# FP_connectors.net
KiCad netlist of a schematic drawn in Altium Designer
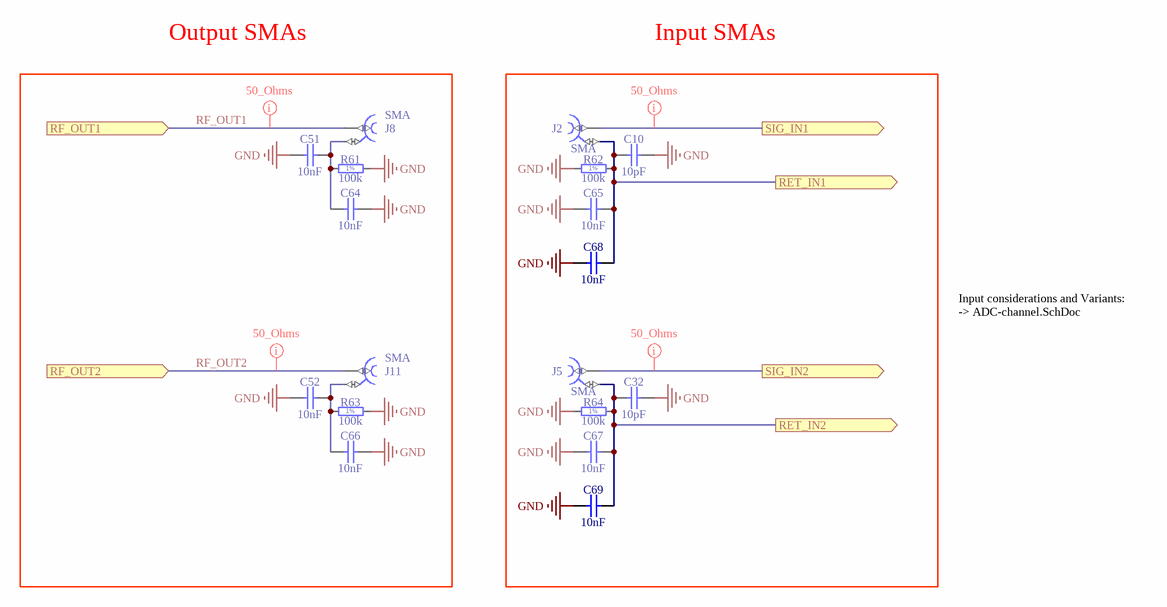
[diagram p0: FP_connectors.SchDoc]

(export (version "E")
  (design (tool "Eeschema 10.0.6"))
  (components
    (comp (ref "C10")
      (value "10pF")
      (footprint "CAPC1005X55N")
      (description "Non-polarised capacitor")
      (fields
        (field (name "PART NUMBER") "CC0402_10PF_50V_5%_C0G")
        (field (name "VOLTAGE") "50V")
        (field (name "AUTHOR") "CERN DEM JLC")
      )
      (libsource (lib "Capacitors") (part "Capacitor - non polarized"))
    )
    (comp (ref "C32")
      (value "10pF")
      (footprint "CAPC1005X55N")
      (description "Non-polarised capacitor")
      (fields
        (field (name "PART NUMBER") "CC0402_10PF_50V_5%_C0G")
        (field (name "VOLTAGE") "50V")
        (field (name "AUTHOR") "CERN DEM JLC")
      )
      (libsource (lib "Capacitors") (part "Capacitor - non polarized"))
    )
    (comp (ref "C51")
      (value "10nF")
      (footprint "CAPC1005X55N")
      (description "Non-polarised capacitor")
      (fields
        (field (name "PART NUMBER") "CC0402_10NF_16V_10%_X7R")
        (field (name "VOLTAGE") "16V")
        (field (name "AUTHOR") "CERN DEM JLC")
      )
      (libsource (lib "Capacitors") (part "Capacitor - non polarized"))
    )
    (comp (ref "C52")
      (value "10nF")
      (footprint "CAPC1005X55N")
      (description "Non-polarised capacitor")
      (fields
        (field (name "PART NUMBER") "CC0402_10NF_16V_10%_X7R")
        (field (name "VOLTAGE") "16V")
        (field (name "AUTHOR") "CERN DEM JLC")
      )
      (libsource (lib "Capacitors") (part "Capacitor - non polarized"))
    )
    (comp (ref "C64")
      (value "10nF")
      (footprint "CAPC1005X55N")
      (description "Non-polarised capacitor")
      (fields
        (field (name "PART NUMBER") "CC0402_10NF_16V_10%_X7R")
        (field (name "VOLTAGE") "16V")
        (field (name "AUTHOR") "CERN DEM JLC")
      )
      (libsource (lib "Capacitors") (part "Capacitor - non polarized"))
    )
    (comp (ref "C65")
      (value "10nF")
      (footprint "CAPC1005X55N")
      (description "Non-polarised capacitor")
      (fields
        (field (name "PART NUMBER") "CC0402_10NF_16V_10%_X7R")
        (field (name "VOLTAGE") "16V")
        (field (name "AUTHOR") "CERN DEM JLC")
      )
      (libsource (lib "Capacitors") (part "Capacitor - non polarized"))
    )
    (comp (ref "C66")
      (value "10nF")
      (footprint "CAPC1005X55N")
      (description "Non-polarised capacitor")
      (fields
        (field (name "PART NUMBER") "CC0402_10NF_16V_10%_X7R")
        (field (name "VOLTAGE") "16V")
        (field (name "AUTHOR") "CERN DEM JLC")
      )
      (libsource (lib "Capacitors") (part "Capacitor - non polarized"))
    )
    (comp (ref "C67")
      (value "10nF")
      (footprint "CAPC1005X55N")
      (description "Non-polarised capacitor")
      (fields
        (field (name "PART NUMBER") "CC0402_10NF_16V_10%_X7R")
        (field (name "VOLTAGE") "16V")
        (field (name "AUTHOR") "CERN DEM JLC")
      )
      (libsource (lib "Capacitors") (part "Capacitor - non polarized"))
    )
    (comp (ref "C68")
      (value "10nF")
      (footprint "CAPC1005X55N")
      (description "Non-polarised capacitor")
      (fields
        (field (name "PART NUMBER") "CC0402_10NF_16V_10%_X7R")
        (field (name "VOLTAGE") "16V")
        (field (name "AUTHOR") "CERN DEM JLC")
      )
      (libsource (lib "Capacitors") (part "Capacitor - non polarized"))
    )
    (comp (ref "C69")
      (value "10nF")
      (footprint "CAPC1005X55N")
      (description "Non-polarised capacitor")
      (fields
        (field (name "PART NUMBER") "CC0402_10NF_16V_10%_X7R")
        (field (name "VOLTAGE") "16V")
        (field (name "AUTHOR") "CERN DEM JLC")
      )
      (libsource (lib "Capacitors") (part "Capacitor - non polarized"))
    )
    (comp (ref "J2")
      (value "SMA")
      (footprint "Telegartner_J01151A0921")
      (description "RiSMA 50 Ohms Right Angle PCB Jack")
      (fields
        (field (name "PART NUMBER") "Telegartner_J01151A0921")
        (field (name "MANUFACTURER") "Telegartner")
        (field (name "AUTHOR") "GK")
      )
      (libsource (lib "LIBRARY_SCH") (part "SMA_RA_J01151A0921"))
    )
    (comp (ref "J5")
      (value "SMA")
      (footprint "Telegartner_J01151A0921")
      (description "RiSMA 50 Ohms Right Angle PCB Jack")
      (fields
        (field (name "PART NUMBER") "Telegartner_J01151A0921")
        (field (name "MANUFACTURER") "Telegartner")
        (field (name "AUTHOR") "GK")
      )
      (libsource (lib "LIBRARY_SCH") (part "SMA_RA_J01151A0921"))
    )
    (comp (ref "J8")
      (value "SMA")
      (footprint "TELEGARTNER_J01151A0451")
      (fields
        (field (name "PART NUMBER") "TELEGARTNER_J01151A0451")
        (field (name "MANUFACTURER") "TELEGARTNER")
        (field (name "MANUFACTURER PART NUMBER") "J01151A0451")
        (field (name "AUTHOR") "CERN DEM JLC")
      )
      (libsource (lib "Connectors") (part "Coax_1Female_1Shield"))
    )
    (comp (ref "J11")
      (value "SMA")
      (footprint "TELEGARTNER_J01151A0451")
      (fields
        (field (name "PART NUMBER") "TELEGARTNER_J01151A0451")
        (field (name "MANUFACTURER") "TELEGARTNER")
        (field (name "MANUFACTURER PART NUMBER") "J01151A0451")
        (field (name "AUTHOR") "CERN DEM JLC")
      )
      (libsource (lib "Connectors") (part "Coax_1Female_1Shield"))
    )
    (comp (ref "R61")
      (value "100k")
      (footprint "RESC1005X40N")
      (description "Resistor - 1%")
      (fields
        (field (name "PART NUMBER") "R0402_100K_1%_0.0625W_100PPM")
        (field (name "POWER") "0.0625W")
        (field (name "AUTHOR") "CERN DEM JLC")
      )
      (libsource (lib "Resistors") (part "Resistor - 1%"))
    )
    (comp (ref "R62")
      (value "100k")
      (footprint "RESC1005X40N")
      (description "Resistor - 1%")
      (fields
        (field (name "PART NUMBER") "R0402_100K_1%_0.0625W_100PPM")
        (field (name "POWER") "0.0625W")
        (field (name "AUTHOR") "CERN DEM JLC")
      )
      (libsource (lib "Resistors") (part "Resistor - 1%"))
    )
    (comp (ref "R63")
      (value "100k")
      (footprint "RESC1005X40N")
      (description "Resistor - 1%")
      (fields
        (field (name "PART NUMBER") "R0402_100K_1%_0.0625W_100PPM")
        (field (name "POWER") "0.0625W")
        (field (name "AUTHOR") "CERN DEM JLC")
      )
      (libsource (lib "Resistors") (part "Resistor - 1%"))
    )
    (comp (ref "R64")
      (value "100k")
      (footprint "RESC1005X40N")
      (description "Resistor - 1%")
      (fields
        (field (name "PART NUMBER") "R0402_100K_1%_0.0625W_100PPM")
        (field (name "POWER") "0.0625W")
        (field (name "AUTHOR") "CERN DEM JLC")
      )
      (libsource (lib "Resistors") (part "Resistor - 1%"))
    )
  )
  (nets
    (net (code "1") (name "/RET_IN1") (class "Default")
      (node (ref "C10") (pin "1") (pinfunction "1_1") (pintype "passive"))
      (node (ref "C65") (pin "2") (pinfunction "2_2") (pintype "passive"))
      (node (ref "C68") (pin "2") (pinfunction "2_2") (pintype "passive"))
      (node (ref "J2") (pin "2") (pinfunction "2_2") (pintype "bidirectional"))
      (node (ref "R62") (pin "2") (pinfunction "2_2") (pintype "passive"))
    )
    (net (code "2") (name "/RET_IN2") (class "Default")
      (node (ref "C32") (pin "1") (pinfunction "1_1") (pintype "passive"))
      (node (ref "C67") (pin "2") (pinfunction "2_2") (pintype "passive"))
      (node (ref "C69") (pin "2") (pinfunction "2_2") (pintype "passive"))
      (node (ref "J5") (pin "2") (pinfunction "2_2") (pintype "bidirectional"))
      (node (ref "R64") (pin "2") (pinfunction "2_2") (pintype "passive"))
    )
    (net (code "3") (name "/RF_OUT1") (class "Default")
      (node (ref "J8") (pin "1") (pinfunction "1_1") (pintype "bidirectional"))
    )
    (net (code "4") (name "/RF_OUT2") (class "Default")
      (node (ref "J11") (pin "1") (pinfunction "1_1") (pintype "bidirectional"))
    )
    (net (code "5") (name "/SIG_IN1") (class "Default")
      (node (ref "J2") (pin "1") (pinfunction "1_1") (pintype "bidirectional"))
    )
    (net (code "6") (name "/SIG_IN2") (class "Default")
      (node (ref "J5") (pin "1") (pinfunction "1_1") (pintype "bidirectional"))
    )
    (net (code "7") (name "GND") (class "Default")
      (node (ref "C10") (pin "2") (pinfunction "2_2") (pintype "passive"))
      (node (ref "C32") (pin "2") (pinfunction "2_2") (pintype "passive"))
      (node (ref "C51") (pin "1") (pinfunction "1_1") (pintype "passive"))
      (node (ref "C52") (pin "1") (pinfunction "1_1") (pintype "passive"))
      (node (ref "C64") (pin "2") (pinfunction "2_2") (pintype "passive"))
      (node (ref "C65") (pin "1") (pinfunction "1_1") (pintype "passive"))
      (node (ref "C66") (pin "2") (pinfunction "2_2") (pintype "passive"))
      (node (ref "C67") (pin "1") (pinfunction "1_1") (pintype "passive"))
      (node (ref "C68") (pin "1") (pinfunction "1_1") (pintype "passive"))
      (node (ref "C69") (pin "1") (pinfunction "1_1") (pintype "passive"))
      (node (ref "R61") (pin "1") (pinfunction "1_1") (pintype "passive"))
      (node (ref "R62") (pin "1") (pinfunction "1_1") (pintype "passive"))
      (node (ref "R63") (pin "1") (pinfunction "1_1") (pintype "passive"))
      (node (ref "R64") (pin "1") (pinfunction "1_1") (pintype "passive"))
    )
    (net (code "8") (name "Net-(C51-Pad2)") (class "Default")
      (node (ref "C51") (pin "2") (pinfunction "2_2") (pintype "passive"))
      (node (ref "C64") (pin "1") (pinfunction "1_1") (pintype "passive"))
      (node (ref "J8") (pin "2") (pinfunction "2_2") (pintype "bidirectional"))
      (node (ref "R61") (pin "2") (pinfunction "2_2") (pintype "passive"))
    )
    (net (code "9") (name "Net-(C52-Pad2)") (class "Default")
      (node (ref "C52") (pin "2") (pinfunction "2_2") (pintype "passive"))
      (node (ref "C66") (pin "1") (pinfunction "1_1") (pintype "passive"))
      (node (ref "J11") (pin "2") (pinfunction "2_2") (pintype "bidirectional"))
      (node (ref "R63") (pin "2") (pinfunction "2_2") (pintype "passive"))
    )
  )
)
